# Cube.net
KiCad netlist of a schematic drawn in Altium Designer
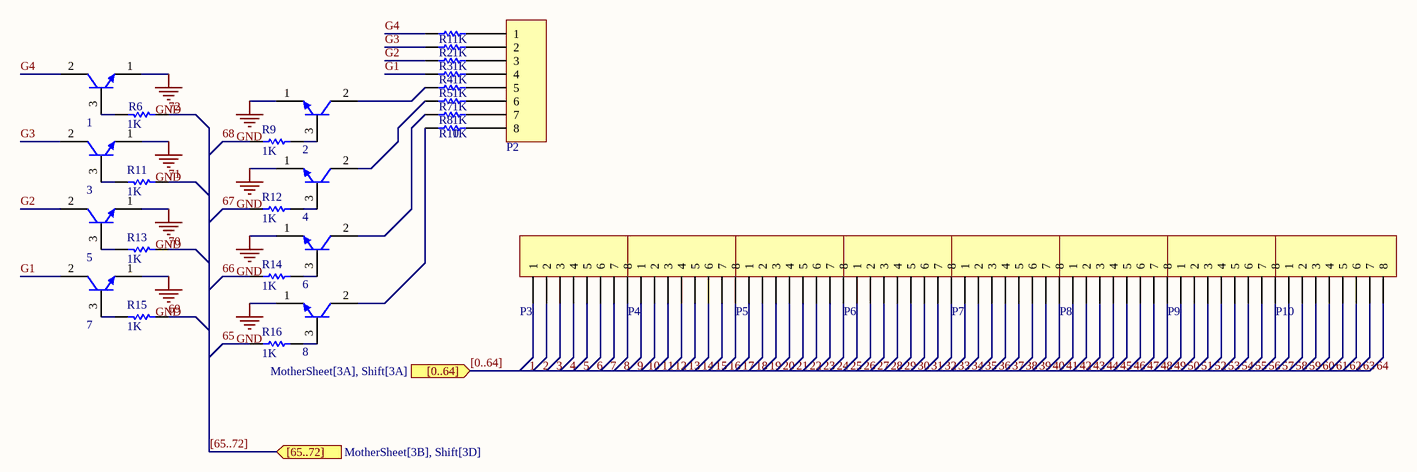
[diagram p0: Cube.SchDoc]

(export (version "E")
  (design (tool "Eeschema 10.0.6"))
  (components
    (comp (ref "1")
      (value "C1815")
      (footprint "QTO-92")
      (description "NPN Bipolar Transistor")
      (libsource (lib "PIF_Library") (part "C1815"))
    )
    (comp (ref "2")
      (value "C1815")
      (footprint "QTO-92")
      (description "NPN Bipolar Transistor")
      (libsource (lib "PIF_Library") (part "C1815"))
    )
    (comp (ref "3")
      (value "C1815")
      (footprint "QTO-92")
      (description "NPN Bipolar Transistor")
      (libsource (lib "PIF_Library") (part "C1815"))
    )
    (comp (ref "4")
      (value "C1815")
      (footprint "QTO-92")
      (description "NPN Bipolar Transistor")
      (libsource (lib "PIF_Library") (part "C1815"))
    )
    (comp (ref "5")
      (value "C1815")
      (footprint "QTO-92")
      (description "NPN Bipolar Transistor")
      (libsource (lib "PIF_Library") (part "C1815"))
    )
    (comp (ref "6")
      (value "C1815")
      (footprint "QTO-92")
      (description "NPN Bipolar Transistor")
      (libsource (lib "PIF_Library") (part "C1815"))
    )
    (comp (ref "7")
      (value "C1815")
      (footprint "QTO-92")
      (description "NPN Bipolar Transistor")
      (libsource (lib "PIF_Library") (part "C1815"))
    )
    (comp (ref "8")
      (value "C1815")
      (footprint "QTO-92")
      (description "NPN Bipolar Transistor")
      (libsource (lib "PIF_Library") (part "C1815"))
    )
    (comp (ref "P2")
      (value "Header 8")
      (footprint "JP8")
      (description "Header, 8-Pin")
      (fields (field (name "PUBLISHER") "Altium Limited"))
      (libsource (lib "") (part "Header 8_1"))
    )
    (comp (ref "P3")
      (value "Header 8")
      (footprint "JP8")
      (description "Header, 8-Pin")
      (fields (field (name "PUBLISHER") "Altium Limited"))
      (libsource (lib "PIF_Library") (part "Header 8"))
    )
    (comp (ref "P4")
      (value "Header 8")
      (footprint "JP8")
      (description "Header, 8-Pin")
      (fields (field (name "PUBLISHER") "Altium Limited"))
      (libsource (lib "PIF_Library") (part "Header 8"))
    )
    (comp (ref "P5")
      (value "Header 8")
      (footprint "JP8")
      (description "Header, 8-Pin")
      (fields (field (name "PUBLISHER") "Altium Limited"))
      (libsource (lib "PIF_Library") (part "Header 8"))
    )
    (comp (ref "P6")
      (value "Header 8")
      (footprint "JP8")
      (description "Header, 8-Pin")
      (fields (field (name "PUBLISHER") "Altium Limited"))
      (libsource (lib "PIF_Library") (part "Header 8"))
    )
    (comp (ref "P7")
      (value "Header 8")
      (footprint "JP8")
      (description "Header, 8-Pin")
      (fields (field (name "PUBLISHER") "Altium Limited"))
      (libsource (lib "PIF_Library") (part "Header 8"))
    )
    (comp (ref "P8")
      (value "Header 8")
      (footprint "JP8")
      (description "Header, 8-Pin")
      (fields (field (name "PUBLISHER") "Altium Limited"))
      (libsource (lib "PIF_Library") (part "Header 8"))
    )
    (comp (ref "P9")
      (value "Header 8")
      (footprint "JP8")
      (description "Header, 8-Pin")
      (fields (field (name "PUBLISHER") "Altium Limited"))
      (libsource (lib "PIF_Library") (part "Header 8"))
    )
    (comp (ref "P10")
      (value "Header 8")
      (footprint "JP8")
      (description "Header, 8-Pin")
      (fields (field (name "PUBLISHER") "Altium Limited"))
      (libsource (lib "PIF_Library") (part "Header 8"))
    )
    (comp (ref "R1")
      (value "1K")
      (footprint "RES 1/2W")
      (description "Resistor")
      (fields (field (name "Comment") "RESISTOR"))
      (libsource (lib "PIF_Library") (part "RESISTOR"))
    )
    (comp (ref "R2")
      (value "1K")
      (footprint "RES 1/2W")
      (description "Resistor")
      (fields (field (name "Comment") "RESISTOR"))
      (libsource (lib "PIF_Library") (part "RESISTOR"))
    )
    (comp (ref "R3")
      (value "1K")
      (footprint "RES 1/2W")
      (description "Resistor")
      (fields (field (name "Comment") "RESISTOR"))
      (libsource (lib "PIF_Library") (part "RESISTOR"))
    )
    (comp (ref "R4")
      (value "1K")
      (footprint "RES 1/2W")
      (description "Resistor")
      (fields (field (name "Comment") "RESISTOR"))
      (libsource (lib "PIF_Library") (part "RESISTOR"))
    )
    (comp (ref "R5")
      (value "1K")
      (footprint "RES 1/2W")
      (description "Resistor")
      (fields (field (name "Comment") "RESISTOR"))
      (libsource (lib "PIF_Library") (part "RESISTOR"))
    )
    (comp (ref "R6")
      (value "1K")
      (footprint "RES 1/2W")
      (description "Resistor")
      (fields (field (name "Comment") "RESISTOR"))
      (libsource (lib "PIF_Library") (part "RESISTOR"))
    )
    (comp (ref "R7")
      (value "1K")
      (footprint "RES 1/2W")
      (description "Resistor")
      (fields (field (name "Comment") "RESISTOR"))
      (libsource (lib "PIF_Library") (part "RESISTOR"))
    )
    (comp (ref "R8")
      (value "1K")
      (footprint "RES 1/2W")
      (description "Resistor")
      (fields (field (name "Comment") "RESISTOR"))
      (libsource (lib "PIF_Library") (part "RESISTOR"))
    )
    (comp (ref "R9")
      (value "1K")
      (footprint "RES-SM-0805")
      (description "Resistor")
      (fields (field (name "Comment") "RESISTOR SMD"))
      (libsource (lib "PIF_Library") (part "RESISTOR SMD"))
    )
    (comp (ref "R10")
      (value "1K")
      (footprint "RES 1/2W")
      (description "Resistor")
      (fields (field (name "Comment") "RESISTOR"))
      (libsource (lib "PIF_Library") (part "RESISTOR"))
    )
    (comp (ref "R11")
      (value "1K")
      (footprint "RES 1/2W")
      (description "Resistor")
      (fields (field (name "Comment") "RESISTOR"))
      (libsource (lib "PIF_Library") (part "RESISTOR"))
    )
    (comp (ref "R12")
      (value "1K")
      (footprint "RES 1/2W")
      (description "Resistor")
      (fields (field (name "Comment") "RESISTOR"))
      (libsource (lib "PIF_Library") (part "RESISTOR"))
    )
    (comp (ref "R13")
      (value "1K")
      (footprint "RES 1/2W")
      (description "Resistor")
      (fields (field (name "Comment") "RESISTOR"))
      (libsource (lib "PIF_Library") (part "RESISTOR"))
    )
    (comp (ref "R14")
      (value "1K")
      (footprint "RES 1/2W")
      (description "Resistor")
      (fields (field (name "Comment") "RESISTOR"))
      (libsource (lib "PIF_Library") (part "RESISTOR"))
    )
    (comp (ref "R15")
      (value "1K")
      (footprint "RES 1/2W")
      (description "Resistor")
      (fields (field (name "Comment") "RESISTOR"))
      (libsource (lib "PIF_Library") (part "RESISTOR"))
    )
    (comp (ref "R16")
      (value "1K")
      (footprint "RES 1/2W")
      (description "Resistor")
      (fields (field (name "Comment") "RESISTOR"))
      (libsource (lib "PIF_Library") (part "RESISTOR"))
    )
  )
  (nets
    (net (code "2") (name "/1") (class "Default")
      (node (ref "P3") (pin "1") (pinfunction "1_1") (pintype "passive"))
    )
    (net (code "3") (name "/2") (class "Default")
      (node (ref "P3") (pin "2") (pinfunction "2_2") (pintype "passive"))
    )
    (net (code "4") (name "/3") (class "Default")
      (node (ref "P3") (pin "3") (pinfunction "3_3") (pintype "passive"))
    )
    (net (code "5") (name "/4") (class "Default")
      (node (ref "P3") (pin "4") (pinfunction "4_4") (pintype "passive"))
    )
    (net (code "6") (name "/5") (class "Default")
      (node (ref "P3") (pin "5") (pinfunction "5_5") (pintype "passive"))
    )
    (net (code "7") (name "/6") (class "Default")
      (node (ref "P3") (pin "6") (pinfunction "6_6") (pintype "passive"))
    )
    (net (code "8") (name "/7") (class "Default")
      (node (ref "P3") (pin "7") (pinfunction "7_7") (pintype "passive"))
    )
    (net (code "9") (name "/8") (class "Default")
      (node (ref "P3") (pin "8") (pinfunction "8_8") (pintype "passive"))
    )
    (net (code "10") (name "/9") (class "Default")
      (node (ref "P4") (pin "1") (pinfunction "1_1") (pintype "passive"))
    )
    (net (code "11") (name "/10") (class "Default")
      (node (ref "P4") (pin "2") (pinfunction "2_2") (pintype "passive"))
    )
    (net (code "12") (name "/11") (class "Default")
      (node (ref "P4") (pin "3") (pinfunction "3_3") (pintype "passive"))
    )
    (net (code "13") (name "/12") (class "Default")
      (node (ref "P4") (pin "4") (pinfunction "4_4") (pintype "passive"))
    )
    (net (code "14") (name "/13") (class "Default")
      (node (ref "P4") (pin "5") (pinfunction "5_5") (pintype "passive"))
    )
    (net (code "15") (name "/14") (class "Default")
      (node (ref "P4") (pin "6") (pinfunction "6_6") (pintype "passive"))
    )
    (net (code "16") (name "/15") (class "Default")
      (node (ref "P4") (pin "7") (pinfunction "7_7") (pintype "passive"))
    )
    (net (code "17") (name "/16") (class "Default")
      (node (ref "P4") (pin "8") (pinfunction "8_8") (pintype "passive"))
    )
    (net (code "18") (name "/17") (class "Default")
      (node (ref "P5") (pin "1") (pinfunction "1_1") (pintype "passive"))
    )
    (net (code "19") (name "/18") (class "Default")
      (node (ref "P5") (pin "2") (pinfunction "2_2") (pintype "passive"))
    )
    (net (code "20") (name "/19") (class "Default")
      (node (ref "P5") (pin "3") (pinfunction "3_3") (pintype "passive"))
    )
    (net (code "21") (name "/20") (class "Default")
      (node (ref "P5") (pin "4") (pinfunction "4_4") (pintype "passive"))
    )
    (net (code "22") (name "/21") (class "Default")
      (node (ref "P5") (pin "5") (pinfunction "5_5") (pintype "passive"))
    )
    (net (code "23") (name "/22") (class "Default")
      (node (ref "P5") (pin "6") (pinfunction "6_6") (pintype "passive"))
    )
    (net (code "24") (name "/23") (class "Default")
      (node (ref "P5") (pin "7") (pinfunction "7_7") (pintype "passive"))
    )
    (net (code "25") (name "/24") (class "Default")
      (node (ref "P5") (pin "8") (pinfunction "8_8") (pintype "passive"))
    )
    (net (code "26") (name "/25") (class "Default")
      (node (ref "P6") (pin "1") (pinfunction "1_1") (pintype "passive"))
    )
    (net (code "27") (name "/26") (class "Default")
      (node (ref "P6") (pin "2") (pinfunction "2_2") (pintype "passive"))
    )
    (net (code "28") (name "/27") (class "Default")
      (node (ref "P6") (pin "3") (pinfunction "3_3") (pintype "passive"))
    )
    (net (code "29") (name "/28") (class "Default")
      (node (ref "P6") (pin "4") (pinfunction "4_4") (pintype "passive"))
    )
    (net (code "30") (name "/29") (class "Default")
      (node (ref "P6") (pin "5") (pinfunction "5_5") (pintype "passive"))
    )
    (net (code "31") (name "/30") (class "Default")
      (node (ref "P6") (pin "6") (pinfunction "6_6") (pintype "passive"))
    )
    (net (code "32") (name "/31") (class "Default")
      (node (ref "P6") (pin "7") (pinfunction "7_7") (pintype "passive"))
    )
    (net (code "33") (name "/32") (class "Default")
      (node (ref "P6") (pin "8") (pinfunction "8_8") (pintype "passive"))
    )
    (net (code "34") (name "/33") (class "Default")
      (node (ref "P7") (pin "1") (pinfunction "1_1") (pintype "passive"))
    )
    (net (code "35") (name "/34") (class "Default")
      (node (ref "P7") (pin "2") (pinfunction "2_2") (pintype "passive"))
    )
    (net (code "36") (name "/35") (class "Default")
      (node (ref "P7") (pin "3") (pinfunction "3_3") (pintype "passive"))
    )
    (net (code "37") (name "/36") (class "Default")
      (node (ref "P7") (pin "4") (pinfunction "4_4") (pintype "passive"))
    )
    (net (code "38") (name "/37") (class "Default")
      (node (ref "P7") (pin "5") (pinfunction "5_5") (pintype "passive"))
    )
    (net (code "39") (name "/38") (class "Default")
      (node (ref "P7") (pin "6") (pinfunction "6_6") (pintype "passive"))
    )
    (net (code "40") (name "/39") (class "Default")
      (node (ref "P7") (pin "7") (pinfunction "7_7") (pintype "passive"))
    )
    (net (code "41") (name "/40") (class "Default")
      (node (ref "P7") (pin "8") (pinfunction "8_8") (pintype "passive"))
    )
    (net (code "42") (name "/41") (class "Default")
      (node (ref "P8") (pin "1") (pinfunction "1_1") (pintype "passive"))
    )
    (net (code "43") (name "/42") (class "Default")
      (node (ref "P8") (pin "2") (pinfunction "2_2") (pintype "passive"))
    )
    (net (code "44") (name "/43") (class "Default")
      (node (ref "P8") (pin "3") (pinfunction "3_3") (pintype "passive"))
    )
    (net (code "45") (name "/44") (class "Default")
      (node (ref "P8") (pin "4") (pinfunction "4_4") (pintype "passive"))
    )
    (net (code "46") (name "/45") (class "Default")
      (node (ref "P8") (pin "5") (pinfunction "5_5") (pintype "passive"))
    )
    (net (code "47") (name "/46") (class "Default")
      (node (ref "P8") (pin "6") (pinfunction "6_6") (pintype "passive"))
    )
    (net (code "48") (name "/47") (class "Default")
      (node (ref "P8") (pin "7") (pinfunction "7_7") (pintype "passive"))
    )
    (net (code "49") (name "/48") (class "Default")
      (node (ref "P8") (pin "8") (pinfunction "8_8") (pintype "passive"))
    )
    (net (code "50") (name "/49") (class "Default")
      (node (ref "P9") (pin "1") (pinfunction "1_1") (pintype "passive"))
    )
    (net (code "51") (name "/50") (class "Default")
      (node (ref "P9") (pin "2") (pinfunction "2_2") (pintype "passive"))
    )
    (net (code "52") (name "/51") (class "Default")
      (node (ref "P9") (pin "3") (pinfunction "3_3") (pintype "passive"))
    )
    (net (code "53") (name "/52") (class "Default")
      (node (ref "P9") (pin "4") (pinfunction "4_4") (pintype "passive"))
    )
    (net (code "54") (name "/53") (class "Default")
      (node (ref "P9") (pin "5") (pinfunction "5_5") (pintype "passive"))
    )
    (net (code "55") (name "/54") (class "Default")
      (node (ref "P9") (pin "6") (pinfunction "6_6") (pintype "passive"))
    )
    (net (code "56") (name "/55") (class "Default")
      (node (ref "P9") (pin "7") (pinfunction "7_7") (pintype "passive"))
    )
    (net (code "57") (name "/56") (class "Default")
      (node (ref "P9") (pin "8") (pinfunction "8_8") (pintype "passive"))
    )
    (net (code "58") (name "/57") (class "Default")
      (node (ref "P10") (pin "1") (pinfunction "1_1") (pintype "passive"))
    )
    (net (code "59") (name "/58") (class "Default")
      (node (ref "P10") (pin "2") (pinfunction "2_2") (pintype "passive"))
    )
    (net (code "60") (name "/59") (class "Default")
      (node (ref "P10") (pin "3") (pinfunction "3_3") (pintype "passive"))
    )
    (net (code "61") (name "/60") (class "Default")
      (node (ref "P10") (pin "4") (pinfunction "4_4") (pintype "passive"))
    )
    (net (code "62") (name "/61") (class "Default")
      (node (ref "P10") (pin "5") (pinfunction "5_5") (pintype "passive"))
    )
    (net (code "63") (name "/62") (class "Default")
      (node (ref "P10") (pin "6") (pinfunction "6_6") (pintype "passive"))
    )
    (net (code "64") (name "/63") (class "Default")
      (node (ref "P10") (pin "7") (pinfunction "7_7") (pintype "passive"))
    )
    (net (code "65") (name "/64") (class "Default")
      (node (ref "P10") (pin "8") (pinfunction "8_8") (pintype "passive"))
    )
    (net (code "66") (name "/65") (class "Default")
      (node (ref "R16") (pin "1") (pinfunction "1_1") (pintype "passive"))
    )
    (net (code "67") (name "/66") (class "Default")
      (node (ref "R14") (pin "1") (pinfunction "1_1") (pintype "passive"))
    )
    (net (code "68") (name "/67") (class "Default")
      (node (ref "R12") (pin "1") (pinfunction "1_1") (pintype "passive"))
    )
    (net (code "69") (name "/68") (class "Default")
      (node (ref "R9") (pin "1") (pinfunction "1_1") (pintype "passive"))
    )
    (net (code "70") (name "/69") (class "Default")
      (node (ref "R15") (pin "1") (pinfunction "1_1") (pintype "passive"))
    )
    (net (code "71") (name "/70") (class "Default")
      (node (ref "R13") (pin "1") (pinfunction "1_1") (pintype "passive"))
    )
    (net (code "72") (name "/71") (class "Default")
      (node (ref "R11") (pin "1") (pinfunction "1_1") (pintype "passive"))
    )
    (net (code "73") (name "/72") (class "Default")
      (node (ref "R6") (pin "1") (pinfunction "1_1") (pintype "passive"))
    )
    (net (code "74") (name "/G1") (class "Default")
      (node (ref "7") (pin "2") (pinfunction "C_2") (pintype "passive"))
      (node (ref "R4") (pin "1") (pinfunction "1_1") (pintype "passive"))
    )
    (net (code "75") (name "/G2") (class "Default")
      (node (ref "5") (pin "2") (pinfunction "C_2") (pintype "passive"))
      (node (ref "R3") (pin "1") (pinfunction "1_1") (pintype "passive"))
    )
    (net (code "76") (name "/G3") (class "Default")
      (node (ref "3") (pin "2") (pinfunction "C_2") (pintype "passive"))
      (node (ref "R2") (pin "1") (pinfunction "1_1") (pintype "passive"))
    )
    (net (code "77") (name "/G4") (class "Default")
      (node (ref "1") (pin "2") (pinfunction "C_2") (pintype "passive"))
      (node (ref "R1") (pin "1") (pinfunction "1_1") (pintype "passive"))
    )
    (net (code "80") (name "GND") (class "Default")
      (node (ref "1") (pin "1") (pinfunction "E_1") (pintype "passive"))
      (node (ref "2") (pin "1") (pinfunction "E_1") (pintype "passive"))
      (node (ref "3") (pin "1") (pinfunction "E_1") (pintype "passive"))
      (node (ref "4") (pin "1") (pinfunction "E_1") (pintype "passive"))
      (node (ref "5") (pin "1") (pinfunction "E_1") (pintype "passive"))
      (node (ref "6") (pin "1") (pinfunction "E_1") (pintype "passive"))
      (node (ref "7") (pin "1") (pinfunction "E_1") (pintype "passive"))
      (node (ref "8") (pin "1") (pinfunction "E_1") (pintype "passive"))
    )
    (net (code "81") (name "Net-(1-B)") (class "Default")
      (node (ref "1") (pin "3") (pinfunction "B_3") (pintype "passive"))
      (node (ref "R6") (pin "2") (pinfunction "2_2") (pintype "passive"))
    )
    (net (code "82") (name "Net-(2-B)") (class "Default")
      (node (ref "2") (pin "3") (pinfunction "B_3") (pintype "passive"))
      (node (ref "R9") (pin "2") (pinfunction "2_2") (pintype "passive"))
    )
    (net (code "83") (name "Net-(2-C)") (class "Default")
      (node (ref "2") (pin "2") (pinfunction "C_2") (pintype "passive"))
      (node (ref "R5") (pin "1") (pinfunction "1_1") (pintype "passive"))
    )
    (net (code "84") (name "Net-(3-B)") (class "Default")
      (node (ref "3") (pin "3") (pinfunction "B_3") (pintype "passive"))
      (node (ref "R11") (pin "2") (pinfunction "2_2") (pintype "passive"))
    )
    (net (code "85") (name "Net-(4-B)") (class "Default")
      (node (ref "4") (pin "3") (pinfunction "B_3") (pintype "passive"))
      (node (ref "R12") (pin "2") (pinfunction "2_2") (pintype "passive"))
    )
    (net (code "86") (name "Net-(4-C)") (class "Default")
      (node (ref "4") (pin "2") (pinfunction "C_2") (pintype "passive"))
      (node (ref "R7") (pin "1") (pinfunction "1_1") (pintype "passive"))
    )
    (net (code "87") (name "Net-(5-B)") (class "Default")
      (node (ref "5") (pin "3") (pinfunction "B_3") (pintype "passive"))
      (node (ref "R13") (pin "2") (pinfunction "2_2") (pintype "passive"))
    )
    (net (code "88") (name "Net-(6-B)") (class "Default")
      (node (ref "6") (pin "3") (pinfunction "B_3") (pintype "passive"))
      (node (ref "R14") (pin "2") (pinfunction "2_2") (pintype "passive"))
    )
    (net (code "89") (name "Net-(6-C)") (class "Default")
      (node (ref "6") (pin "2") (pinfunction "C_2") (pintype "passive"))
      (node (ref "R8") (pin "1") (pinfunction "1_1") (pintype "passive"))
    )
    (net (code "90") (name "Net-(7-B)") (class "Default")
      (node (ref "7") (pin "3") (pinfunction "B_3") (pintype "passive"))
      (node (ref "R15") (pin "2") (pinfunction "2_2") (pintype "passive"))
    )
    (net (code "91") (name "Net-(8-B)") (class "Default")
      (node (ref "8") (pin "3") (pinfunction "B_3") (pintype "passive"))
      (node (ref "R16") (pin "2") (pinfunction "2_2") (pintype "passive"))
    )
    (net (code "92") (name "Net-(8-C)") (class "Default")
      (node (ref "8") (pin "2") (pinfunction "C_2") (pintype "passive"))
      (node (ref "R10") (pin "1") (pinfunction "1_1") (pintype "passive"))
    )
    (net (code "93") (name "Net-(P2-Pad1)") (class "Default")
      (node (ref "P2") (pin "1") (pinfunction "1_1") (pintype "passive"))
      (node (ref "R1") (pin "2") (pinfunction "2_2") (pintype "passive"))
    )
    (net (code "94") (name "Net-(P2-Pad2)") (class "Default")
      (node (ref "P2") (pin "2") (pinfunction "2_2") (pintype "passive"))
      (node (ref "R2") (pin "2") (pinfunction "2_2") (pintype "passive"))
    )
    (net (code "95") (name "Net-(P2-Pad3)") (class "Default")
      (node (ref "P2") (pin "3") (pinfunction "3_3") (pintype "passive"))
      (node (ref "R3") (pin "2") (pinfunction "2_2") (pintype "passive"))
    )
    (net (code "96") (name "Net-(P2-Pad4)") (class "Default")
      (node (ref "P2") (pin "4") (pinfunction "4_4") (pintype "passive"))
      (node (ref "R4") (pin "2") (pinfunction "2_2") (pintype "passive"))
    )
    (net (code "97") (name "Net-(P2-Pad5)") (class "Default")
      (node (ref "P2") (pin "5") (pinfunction "5_5") (pintype "passive"))
      (node (ref "R5") (pin "2") (pinfunction "2_2") (pintype "passive"))
    )
    (net (code "98") (name "Net-(P2-Pad6)") (class "Default")
      (node (ref "P2") (pin "6") (pinfunction "6_6") (pintype "passive"))
      (node (ref "R7") (pin "2") (pinfunction "2_2") (pintype "passive"))
    )
    (net (code "99") (name "Net-(P2-Pad7)") (class "Default")
      (node (ref "P2") (pin "7") (pinfunction "7_7") (pintype "passive"))
      (node (ref "R8") (pin "2") (pinfunction "2_2") (pintype "passive"))
    )
    (net (code "100") (name "Net-(P2-Pad8)") (class "Default")
      (node (ref "P2") (pin "8") (pinfunction "8_8") (pintype "passive"))
      (node (ref "R10") (pin "2") (pinfunction "2_2") (pintype "passive"))
    )
  )
)
